# MCU.net
KiCad netlist of a schematic drawn in Altium Designer
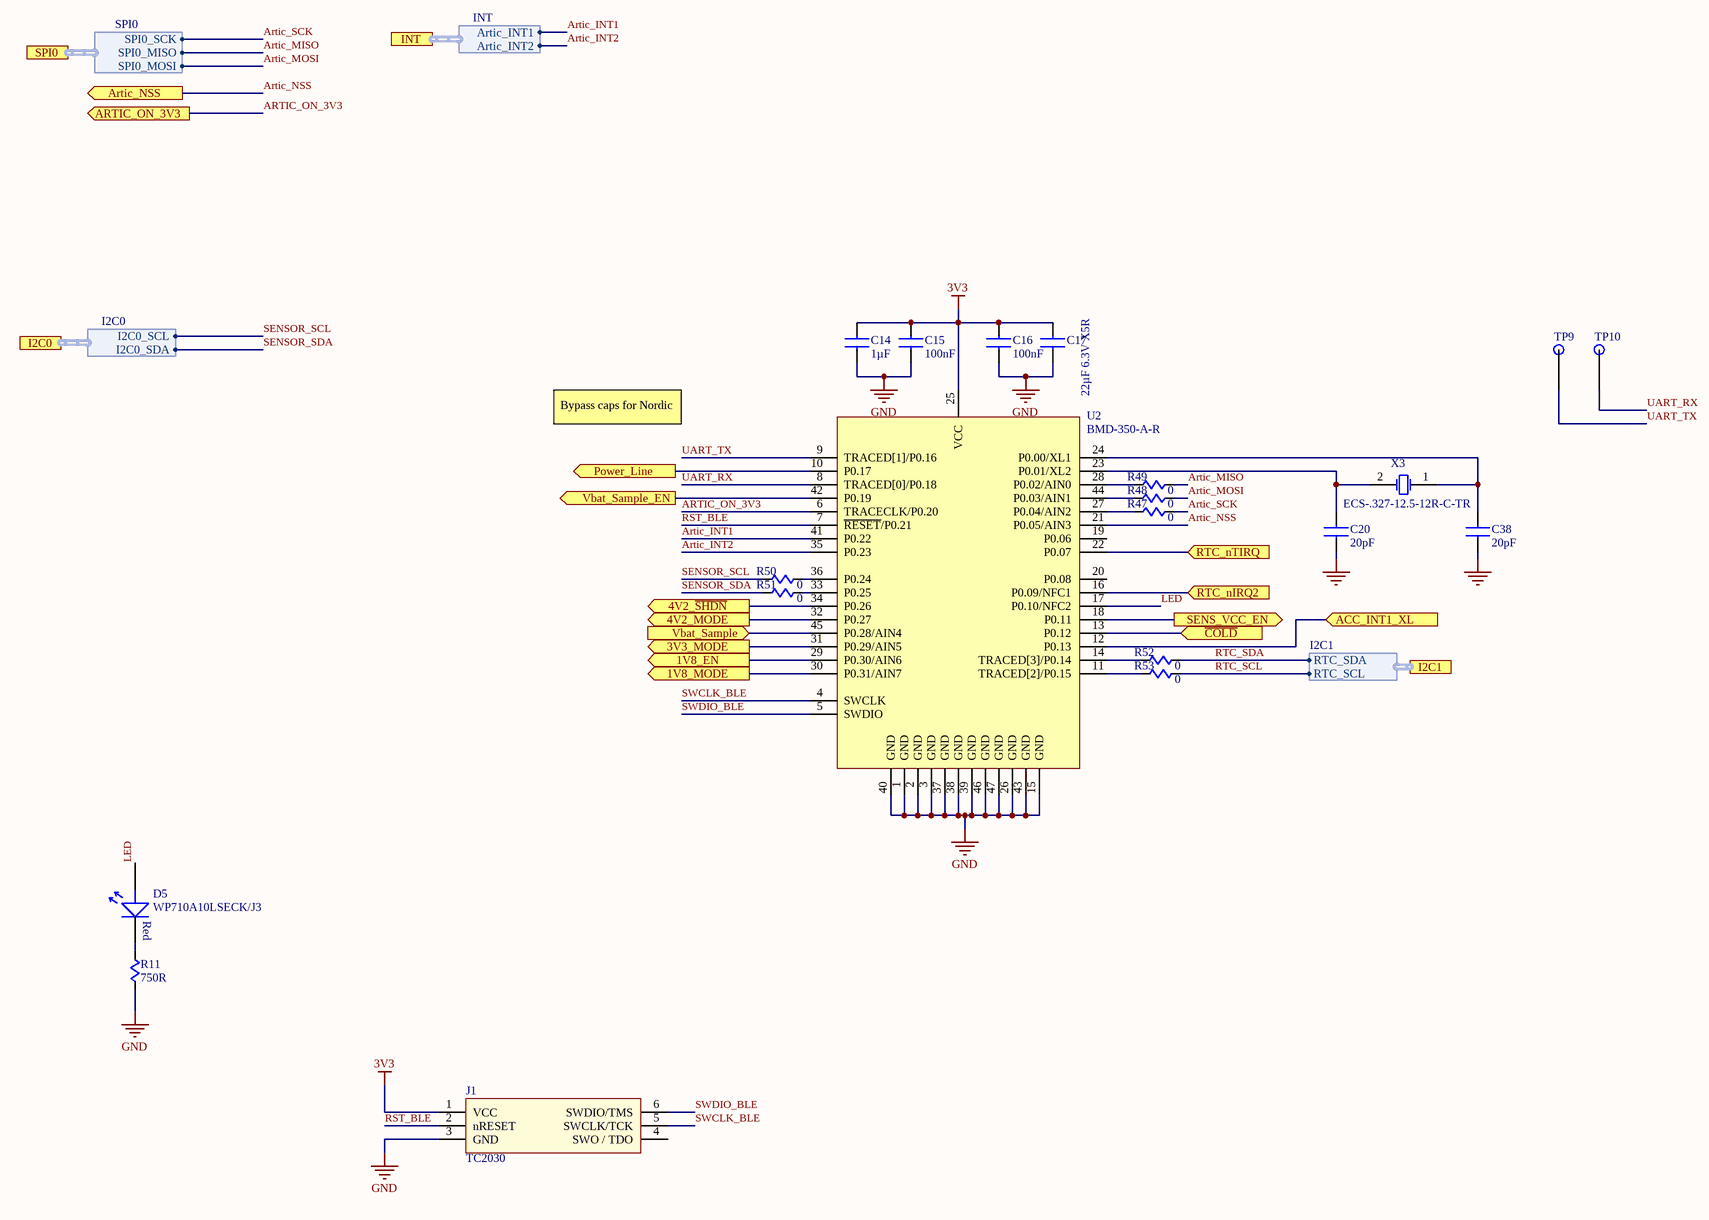
[diagram p0: MCU.SchDoc]

(export (version "E")
  (design (tool "Eeschema 10.0.6"))
  (components
    (comp (ref "C14")
      (value "1µF")
      (footprint "CAPC1005N-0402")
      (description "CAP CER 1UF 6.3V X7R 0402 ±10%")
      (fields
        (field (name "MANUFACTURER") "Samsung Electro-Mechanics America, Inc.")
        (field (name "MANUFACTURER PART NUMBER") "CL05B105KQ5NQNC")
      )
      (libsource (lib "") (part "Component_1_1"))
    )
    (comp (ref "C15")
      (value "100nF")
      (footprint "CAPC1005N-0402")
      (description "CAP CER 0.1UF 10V X7R 0402 ±5%")
      (fields
        (field (name "MANUFACTURER") "Samsung Electro-Mechanics America, Inc.")
        (field (name "MANUFACTURER PART NUMBER") "CL05B104JP5NNNC")
      )
      (libsource (lib "") (part "Component_1_1"))
    )
    (comp (ref "C16")
      (value "100nF")
      (footprint "CAPC1005N-0402")
      (description "CAP CER 0.1UF 10V X7R 0402 ±5%")
      (fields
        (field (name "MANUFACTURER") "Samsung Electro-Mechanics America, Inc.")
        (field (name "MANUFACTURER PART NUMBER") "CL05B104JP5NNNC")
      )
      (libsource (lib "") (part "Component_1_1"))
    )
    (comp (ref "C17")
      (value "22µF 6.3V X5R")
      (footprint "CAPC1608N-0603")
      (description "CAP CER 22UF 6.3V X5R 0603 ±10%")
      (fields
        (field (name "MANUFACTURER") "Samsung Electro-Mechanics America, Inc.")
        (field (name "MANUFACTURER PART NUMBER") "CL10A226KQ8NRNE")
      )
      (libsource (lib "") (part "Component_1_1"))
    )
    (comp (ref "C20")
      (value "20pF")
      (footprint "CAPC1005N-0402")
      (description "CAP CER 20PF 50V C0G/NP0 0402 ±5%")
      (fields
        (field (name "MANUFACTURER") "Samsung Electro-Mechanics America, Inc.")
        (field (name "MANUFACTURER PART NUMBER") "CL05C200JB5NNNC")
      )
      (libsource (lib "") (part "Component_1_1"))
    )
    (comp (ref "C38")
      (value "20pF")
      (footprint "CAPC1005N-0402")
      (description "CAP CER 20PF 50V C0G/NP0 0402 ±5%")
      (fields
        (field (name "MANUFACTURER") "Samsung Electro-Mechanics America, Inc.")
        (field (name "MANUFACTURER PART NUMBER") "CL05C200JB5NNNC")
      )
      (libsource (lib "") (part "Component_1_1"))
    )
    (comp (ref "D5")
      (value "WP710A10LSECK/J3")
      (footprint "T-1 (3mm)")
      (description "Red 625nm LED Indication - Discrete 1.8V Radial")
      (fields (field (name "MANUFACTURER") "Kingbright"))
      (libsource (lib "Misty West") (part "LED_Red"))
    )
    (comp (ref "J1")
      (value "TC2030")
      (footprint "TC2030 - No Clips")
      (fields (field (name "MANUFACTURER") "Tag Connect"))
      (libsource (lib "Misty West") (part "CMP-003-0005-4"))
    )
    (comp (ref "R11")
      (value "750R")
      (footprint "Chip Res 1608_0603 MMC")
      (description "750R 0.1W ±5%")
      (fields
        (field (name "MANUFACTURER") "Yageo")
        (field (name "MANUFACTURER PART NUMBER") "RC0603JR-07750RL")
      )
      (libsource (lib "Misty West") (part "Component_1"))
    )
    (comp (ref "R47")
      (value "0")
      (footprint "RESC0402(1005)_N")
      (description "RES SMD 0.0OHM JUMPER 1/16W 0402")
      (fields
        (field (name "MANUFACTURER") "Yageo")
        (field (name "MANUFACTURER PART NUMBER") "RC0402JR-070RL")
      )
      (libsource (lib "Misty West") (part "Component_1"))
    )
    (comp (ref "R48")
      (value "0")
      (footprint "RESC0402(1005)_N")
      (description "RES SMD 0.0OHM JUMPER 1/16W 0402")
      (fields
        (field (name "MANUFACTURER") "Yageo")
        (field (name "MANUFACTURER PART NUMBER") "RC0402JR-070RL")
      )
      (libsource (lib "Misty West") (part "Component_1"))
    )
    (comp (ref "R49")
      (value "0")
      (footprint "RESC0402(1005)_N")
      (description "RES SMD 0.0OHM JUMPER 1/16W 0402")
      (fields
        (field (name "MANUFACTURER") "Yageo")
        (field (name "MANUFACTURER PART NUMBER") "RC0402JR-070RL")
      )
      (libsource (lib "Misty West") (part "Component_1"))
    )
    (comp (ref "R50")
      (value "0")
      (footprint "RESC0402(1005)_N")
      (description "RES SMD 0.0OHM JUMPER 1/16W 0402")
      (fields
        (field (name "MANUFACTURER") "Yageo")
        (field (name "MANUFACTURER PART NUMBER") "RC0402JR-070RL")
      )
      (libsource (lib "Misty West") (part "Component_1"))
    )
    (comp (ref "R51")
      (value "0")
      (footprint "RESC0402(1005)_N")
      (description "RES SMD 0.0OHM JUMPER 1/16W 0402")
      (fields
        (field (name "MANUFACTURER") "Yageo")
        (field (name "MANUFACTURER PART NUMBER") "RC0402JR-070RL")
      )
      (libsource (lib "Misty West") (part "Component_1"))
    )
    (comp (ref "R52")
      (value "0")
      (footprint "RESC0402(1005)_N")
      (description "RES SMD 0.0OHM JUMPER 1/16W 0402")
      (fields
        (field (name "MANUFACTURER") "Yageo")
        (field (name "MANUFACTURER PART NUMBER") "RC0402JR-070RL")
      )
      (libsource (lib "Misty West") (part "Component_1"))
    )
    (comp (ref "R53")
      (value "0")
      (footprint "RESC0402(1005)_N")
      (description "RES SMD 0.0OHM JUMPER 1/16W 0402")
      (fields
        (field (name "MANUFACTURER") "Yageo")
        (field (name "MANUFACTURER PART NUMBER") "RC0402JR-070RL")
      )
      (libsource (lib "Misty West") (part "Component_1"))
    )
    (comp (ref "TP9")
      (value "~")
      (footprint "TestPoint_1mm")
      (description "Test Point - 1mm pad")
      (libsource (lib "Misty West") (part "TestPoint_NoPart"))
    )
    (comp (ref "TP10")
      (value "~")
      (footprint "TestPoint_1mm")
      (description "Test Point - 1mm pad")
      (libsource (lib "Misty West") (part "TestPoint_NoPart"))
    )
    (comp (ref "U2")
      (value "BMD-350-A-R")
      (footprint "BMD-350")
      (description "MOD BLE 4.2 NORDIC NRF52832 SOC")
      (fields (field (name "MANUFACTURER") "Rigado, Inc."))
      (libsource (lib "Misty West") (part "BMD-350"))
    )
    (comp (ref "X3")
      (value "ECS-.327-12.5-12R-C-TR")
      (footprint "ECS-.327-12.5-12R-C-TR")
      (description "32.768kHz ±10ppm Crystal 12.5pF 70 kOhms 2-SMD, No Lead")
      (fields (field (name "MANUFACTURER") "ECS Inc."))
      (libsource (lib "Misty West") (part "XTAL_1-2-2"))
    )
  )
  (nets
    (net (code "5") (name "/1V8_EN") (class "Default")
      (node (ref "U2") (pin "29") (pinfunction "P0.30/AIN6_29") (pintype "passive"))
    )
    (net (code "6") (name "/1V8_MODE") (class "Default")
      (node (ref "U2") (pin "30") (pinfunction "P0.31/AIN7_30") (pintype "passive"))
    )
    (net (code "7") (name "/3V3_MODE") (class "Default")
      (node (ref "U2") (pin "31") (pinfunction "P0.29/AIN5_31") (pintype "passive"))
    )
    (net (code "8") (name "/4V2_MODE") (class "Default")
      (node (ref "U2") (pin "32") (pinfunction "P0.27_32") (pintype "passive"))
    )
    (net (code "9") (name "/4V2_~{SHDN}") (class "Default")
      (node (ref "U2") (pin "34") (pinfunction "P0.26_34") (pintype "passive"))
    )
    (net (code "10") (name "/ACC_INT1_XL") (class "Default")
      (node (ref "U2") (pin "12") (pinfunction "P0.13_12") (pintype "passive"))
    )
    (net (code "11") (name "/ARTIC_ON_3V3") (class "Default")
      (node (ref "U2") (pin "6") (pinfunction "TRACECLK/P0.20_6") (pintype "passive"))
    )
    (net (code "12") (name "/Artic_INT1") (class "Default")
      (node (ref "U2") (pin "41") (pinfunction "P0.22_41") (pintype "passive"))
    )
    (net (code "13") (name "/Artic_INT2") (class "Default")
      (node (ref "U2") (pin "35") (pinfunction "P0.23_35") (pintype "passive"))
    )
    (net (code "14") (name "/Artic_MISO") (class "Default") (node (ref "R49") (pin "2") (pintype "passive")))
    (net (code "15") (name "/Artic_MOSI") (class "Default") (node (ref "R48") (pin "2") (pintype "passive")))
    (net (code "16") (name "/Artic_NSS") (class "Default")
      (node (ref "U2") (pin "21") (pinfunction "P0.05/AIN3_21") (pintype "passive"))
    )
    (net (code "17") (name "/Artic_SCK") (class "Default") (node (ref "R47") (pin "2") (pintype "passive")))
    (net (code "18") (name "/LED") (class "Default")
      (node (ref "D5") (pin "1") (pinfunction "Anode_1") (pintype "passive"))
      (node (ref "U2") (pin "17") (pinfunction "P0.10/NFC2_17") (pintype "passive"))
    )
    (net (code "19") (name "/Power_Line") (class "Default")
      (node (ref "U2") (pin "10") (pinfunction "P0.17_10") (pintype "passive"))
    )
    (net (code "20") (name "/RST_BLE") (class "Default")
      (node (ref "J1") (pin "2") (pinfunction "nRESET_2") (pintype "passive"))
      (node (ref "U2") (pin "7") (pinfunction "~{RESET}/P0.21_7") (pintype "passive"))
    )
    (net (code "21") (name "/RTC_SCL") (class "Default") (node (ref "R53") (pin "2") (pintype "passive")))
    (net (code "22") (name "/RTC_SDA") (class "Default") (node (ref "R52") (pin "2") (pintype "passive")))
    (net (code "23") (name "/RTC_nIRQ2") (class "Default")
      (node (ref "U2") (pin "16") (pinfunction "P0.09/NFC1_16") (pintype "passive"))
    )
    (net (code "24") (name "/RTC_nTIRQ") (class "Default")
      (node (ref "U2") (pin "22") (pinfunction "P0.07_22") (pintype "passive"))
    )
    (net (code "25") (name "/SENSOR_SCL") (class "Default") (node (ref "R50") (pin "1") (pintype "passive")))
    (net (code "26") (name "/SENSOR_SDA") (class "Default") (node (ref "R51") (pin "1") (pintype "passive")))
    (net (code "27") (name "/SENS_VCC_EN") (class "Default")
      (node (ref "U2") (pin "18") (pinfunction "P0.11_18") (pintype "passive"))
    )
    (net (code "28") (name "/SWCLK_BLE") (class "Default")
      (node (ref "J1") (pin "5") (pinfunction "SWCLK/TCK_5") (pintype "passive"))
      (node (ref "U2") (pin "4") (pinfunction "SWCLK_4") (pintype "passive"))
    )
    (net (code "29") (name "/SWDIO_BLE") (class "Default")
      (node (ref "J1") (pin "6") (pinfunction "SWDIO/TMS_6") (pintype "passive"))
      (node (ref "U2") (pin "5") (pinfunction "SWDIO_5") (pintype "passive"))
    )
    (net (code "30") (name "/UART_RX") (class "Default")
      (node (ref "TP10") (pin "TP") (pinfunction "TP_TP") (pintype "passive"))
      (node (ref "U2") (pin "8") (pinfunction "TRACED[0]/P0.18_8") (pintype "passive"))
    )
    (net (code "31") (name "/UART_TX") (class "Default")
      (node (ref "TP9") (pin "TP") (pinfunction "TP_TP") (pintype "passive"))
      (node (ref "U2") (pin "9") (pinfunction "TRACED[1]/P0.16_9") (pintype "passive"))
    )
    (net (code "32") (name "/Vbat_Sample") (class "Default")
      (node (ref "U2") (pin "45") (pinfunction "P0.28/AIN4_45") (pintype "passive"))
    )
    (net (code "33") (name "/Vbat_Sample_EN") (class "Default")
      (node (ref "U2") (pin "42") (pinfunction "P0.19_42") (pintype "passive"))
    )
    (net (code "38") (name "/~{COLD}") (class "Default")
      (node (ref "U2") (pin "13") (pinfunction "P0.12_13") (pintype "passive"))
    )
    (net (code "39") (name "3V3") (class "Default")
      (node (ref "C14") (pin "1") (pintype "passive"))
      (node (ref "C15") (pin "1") (pintype "passive"))
      (node (ref "C16") (pin "1") (pintype "passive"))
      (node (ref "C17") (pin "1") (pintype "passive"))
      (node (ref "J1") (pin "1") (pinfunction "VCC_1") (pintype "passive"))
      (node (ref "U2") (pin "25") (pinfunction "VCC_25") (pintype "passive"))
    )
    (net (code "40") (name "GND") (class "Default")
      (node (ref "C14") (pin "2") (pintype "passive"))
      (node (ref "C15") (pin "2") (pintype "passive"))
      (node (ref "C16") (pin "2") (pintype "passive"))
      (node (ref "C17") (pin "2") (pintype "passive"))
      (node (ref "C20") (pin "2") (pintype "passive"))
      (node (ref "C38") (pin "2") (pintype "passive"))
      (node (ref "J1") (pin "3") (pinfunction "GND_3") (pintype "passive"))
      (node (ref "R11") (pin "1") (pintype "passive"))
      (node (ref "U2") (pin "1") (pinfunction "GND_1") (pintype "passive"))
      (node (ref "U2") (pin "15") (pinfunction "GND_15") (pintype "passive"))
      (node (ref "U2") (pin "2") (pinfunction "GND_2") (pintype "passive"))
      (node (ref "U2") (pin "26") (pinfunction "GND_26") (pintype "passive"))
      (node (ref "U2") (pin "3") (pinfunction "GND_3") (pintype "passive"))
      (node (ref "U2") (pin "37") (pinfunction "GND_37") (pintype "passive"))
      (node (ref "U2") (pin "38") (pinfunction "GND_38") (pintype "passive"))
      (node (ref "U2") (pin "39") (pinfunction "GND_39") (pintype "passive"))
      (node (ref "U2") (pin "40") (pinfunction "GND_40") (pintype "passive"))
      (node (ref "U2") (pin "43") (pinfunction "GND_43") (pintype "passive"))
      (node (ref "U2") (pin "46") (pinfunction "GND_46") (pintype "passive"))
      (node (ref "U2") (pin "47") (pinfunction "GND_47") (pintype "passive"))
    )
    (net (code "41") (name "Net-(D5-Cathode)") (class "Default")
      (node (ref "D5") (pin "2") (pinfunction "Cathode_2") (pintype "passive"))
      (node (ref "R11") (pin "2") (pintype "passive"))
    )
    (net (code "42") (name "Net-(U2-P0.00{slash}XL1)") (class "Default")
      (node (ref "C38") (pin "1") (pintype "passive"))
      (node (ref "U2") (pin "24") (pinfunction "P0.00/XL1_24") (pintype "passive"))
      (node (ref "X3") (pin "1") (pinfunction "X1_1") (pintype "passive"))
    )
    (net (code "43") (name "Net-(U2-P0.01{slash}XL2)") (class "Default")
      (node (ref "C20") (pin "1") (pintype "passive"))
      (node (ref "U2") (pin "23") (pinfunction "P0.01/XL2_23") (pintype "passive"))
      (node (ref "X3") (pin "2") (pinfunction "X2_2") (pintype "passive"))
    )
    (net (code "44") (name "Net-(U2-P0.02{slash}AIN0)") (class "Default")
      (node (ref "R49") (pin "1") (pintype "passive"))
      (node (ref "U2") (pin "28") (pinfunction "P0.02/AIN0_28") (pintype "passive"))
    )
    (net (code "45") (name "Net-(U2-P0.03{slash}AIN1)") (class "Default")
      (node (ref "R48") (pin "1") (pintype "passive"))
      (node (ref "U2") (pin "44") (pinfunction "P0.03/AIN1_44") (pintype "passive"))
    )
    (net (code "46") (name "Net-(U2-P0.04{slash}AIN2)") (class "Default")
      (node (ref "R47") (pin "1") (pintype "passive"))
      (node (ref "U2") (pin "27") (pinfunction "P0.04/AIN2_27") (pintype "passive"))
    )
    (net (code "47") (name "Net-(U2-P0.24)") (class "Default")
      (node (ref "R50") (pin "2") (pintype "passive"))
      (node (ref "U2") (pin "36") (pinfunction "P0.24_36") (pintype "passive"))
    )
    (net (code "48") (name "Net-(U2-P0.25)") (class "Default")
      (node (ref "R51") (pin "2") (pintype "passive"))
      (node (ref "U2") (pin "33") (pinfunction "P0.25_33") (pintype "passive"))
    )
    (net (code "49") (name "Net-(U2-TRACED[2]{slash}P0.15)") (class "Default")
      (node (ref "R53") (pin "1") (pintype "passive"))
      (node (ref "U2") (pin "11") (pinfunction "TRACED[2]/P0.15_11") (pintype "passive"))
    )
    (net (code "50") (name "Net-(U2-TRACED[3]{slash}P0.14)") (class "Default")
      (node (ref "R52") (pin "1") (pintype "passive"))
      (node (ref "U2") (pin "14") (pinfunction "TRACED[3]/P0.14_14") (pintype "passive"))
    )
    (net (code "51") (name "unconnected-(J1-SWO_{slash}_TDO-Pad4)") (class "Default")
      (node (ref "J1") (pin "4") (pinfunction "SWO_/_TDO_4") (pintype "passive"))
    )
    (net (code "52") (name "unconnected-(U2-P0.06-Pad19)") (class "Default")
      (node (ref "U2") (pin "19") (pinfunction "P0.06_19") (pintype "passive"))
    )
    (net (code "53") (name "unconnected-(U2-P0.08-Pad20)") (class "Default")
      (node (ref "U2") (pin "20") (pinfunction "P0.08_20") (pintype "passive"))
    )
  )
)
